# T245Controller_rev1.net
KiCad netlist of a schematic drawn in EAGLE
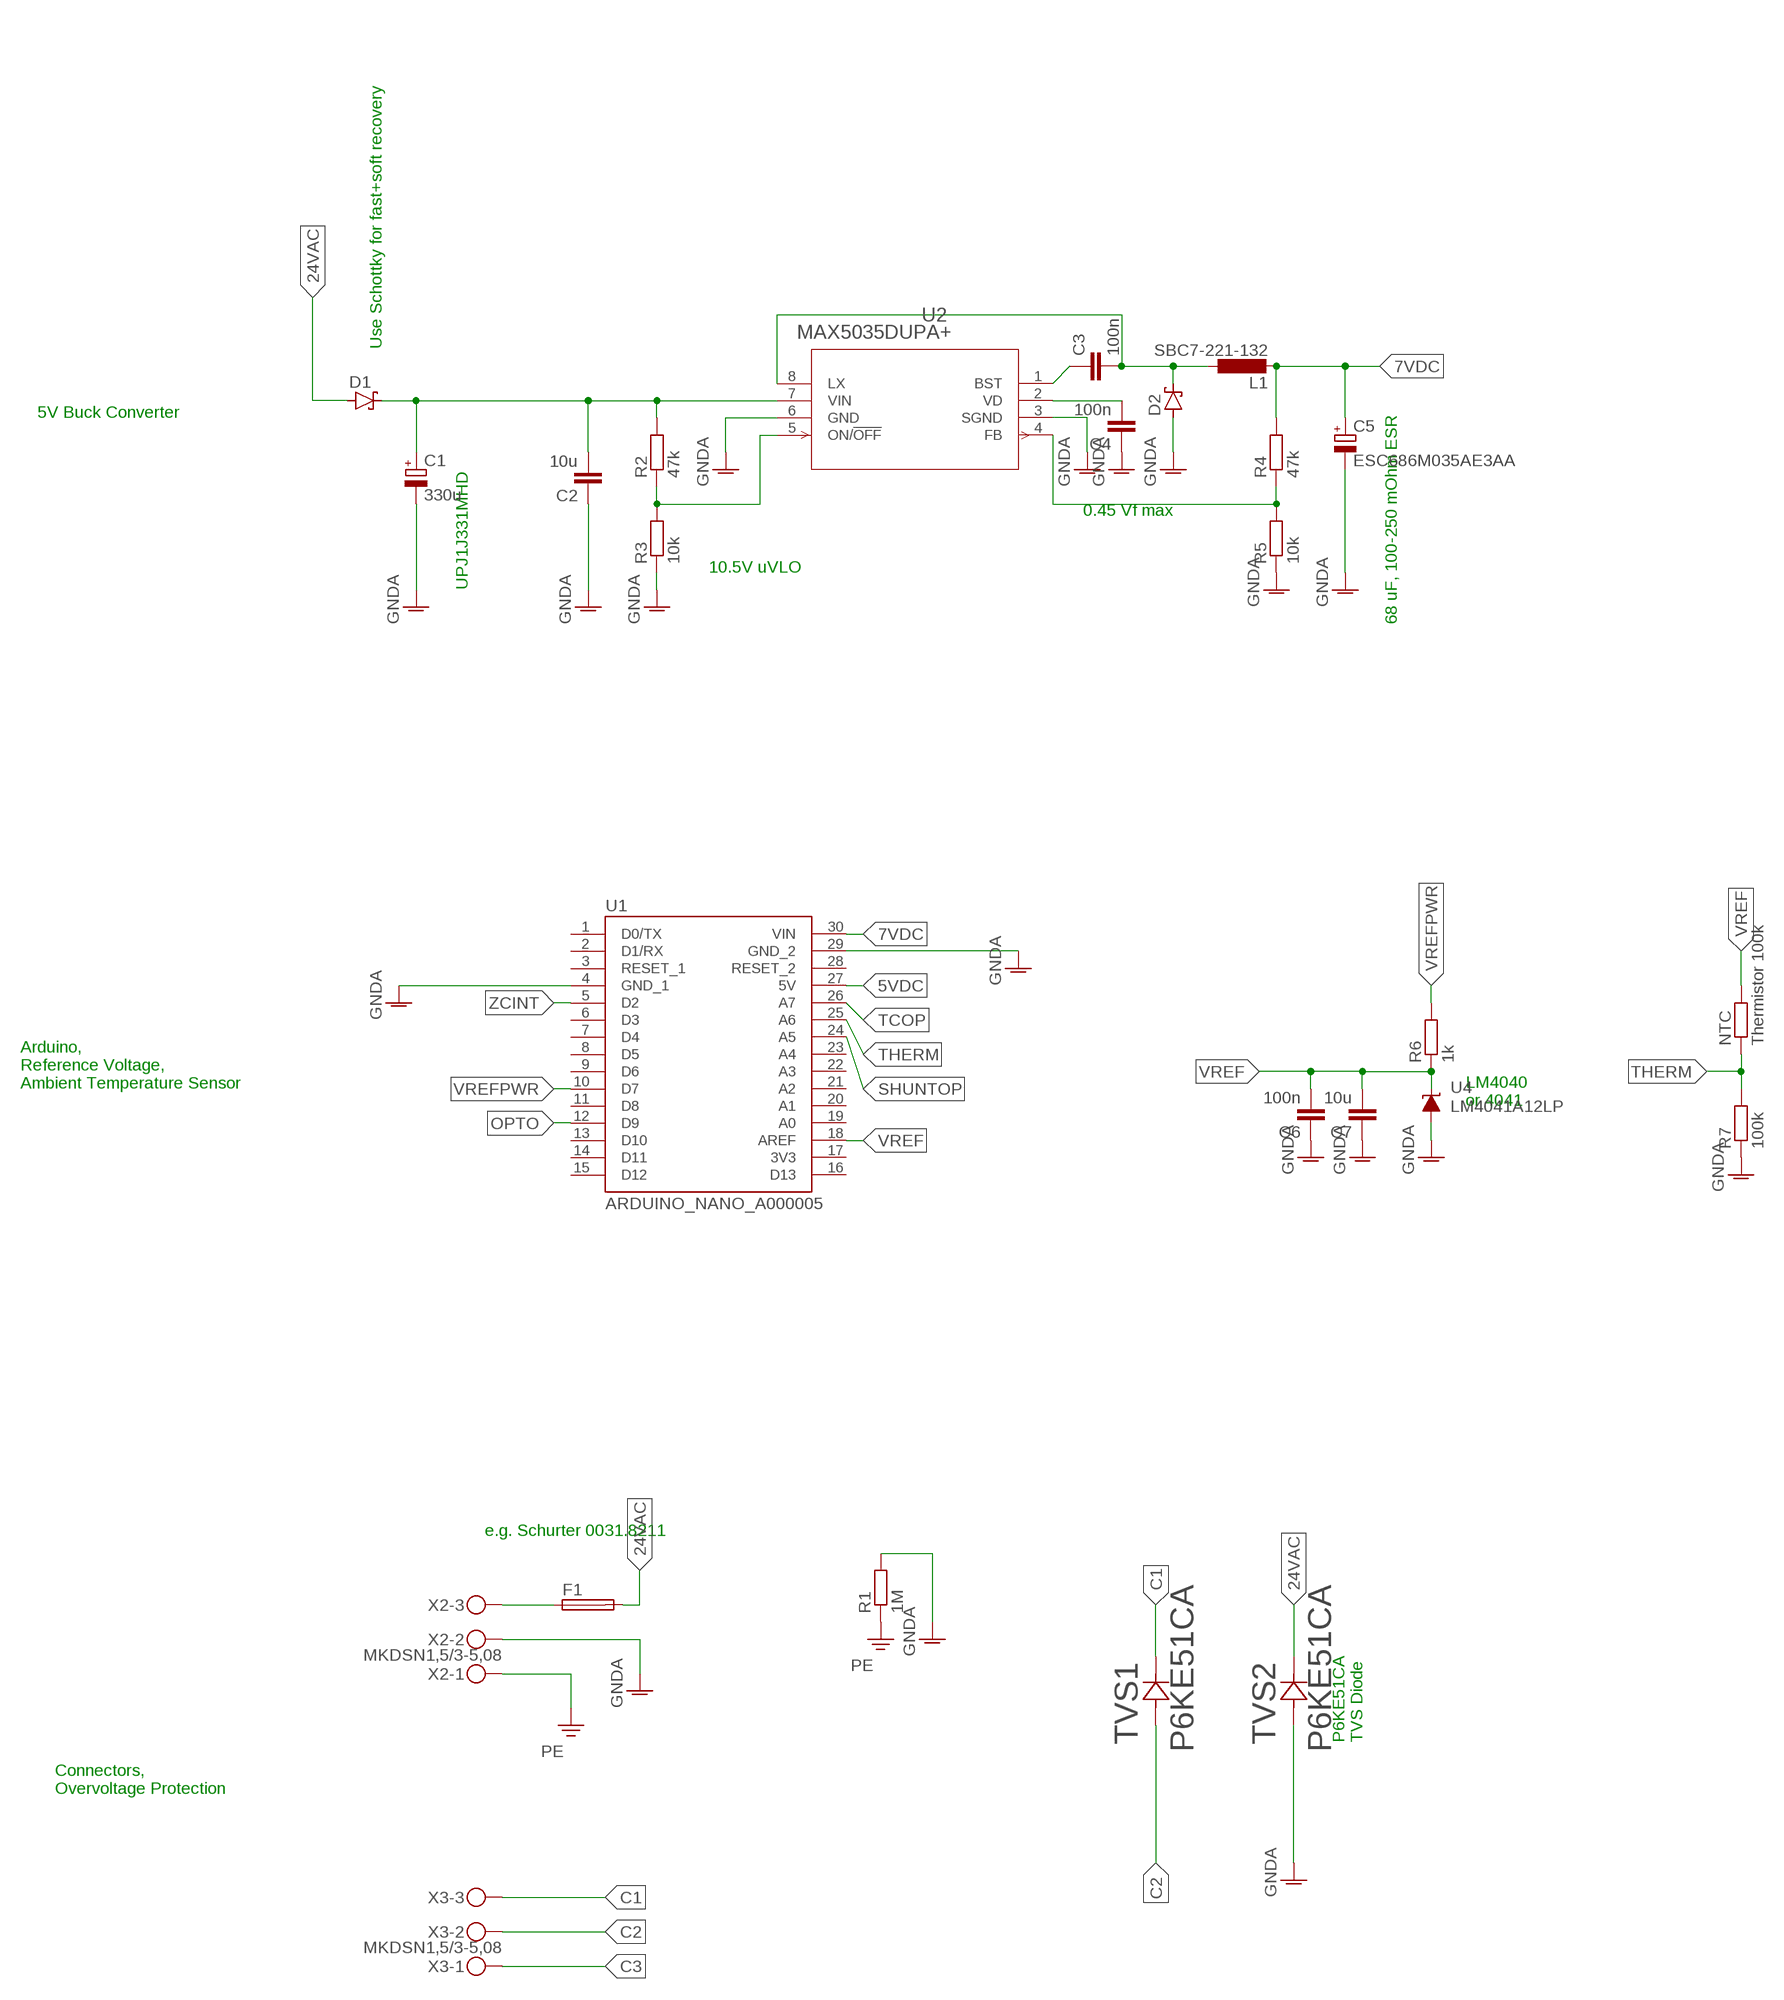
[diagram p0: schematic, sheet 1, part 1 of 2]
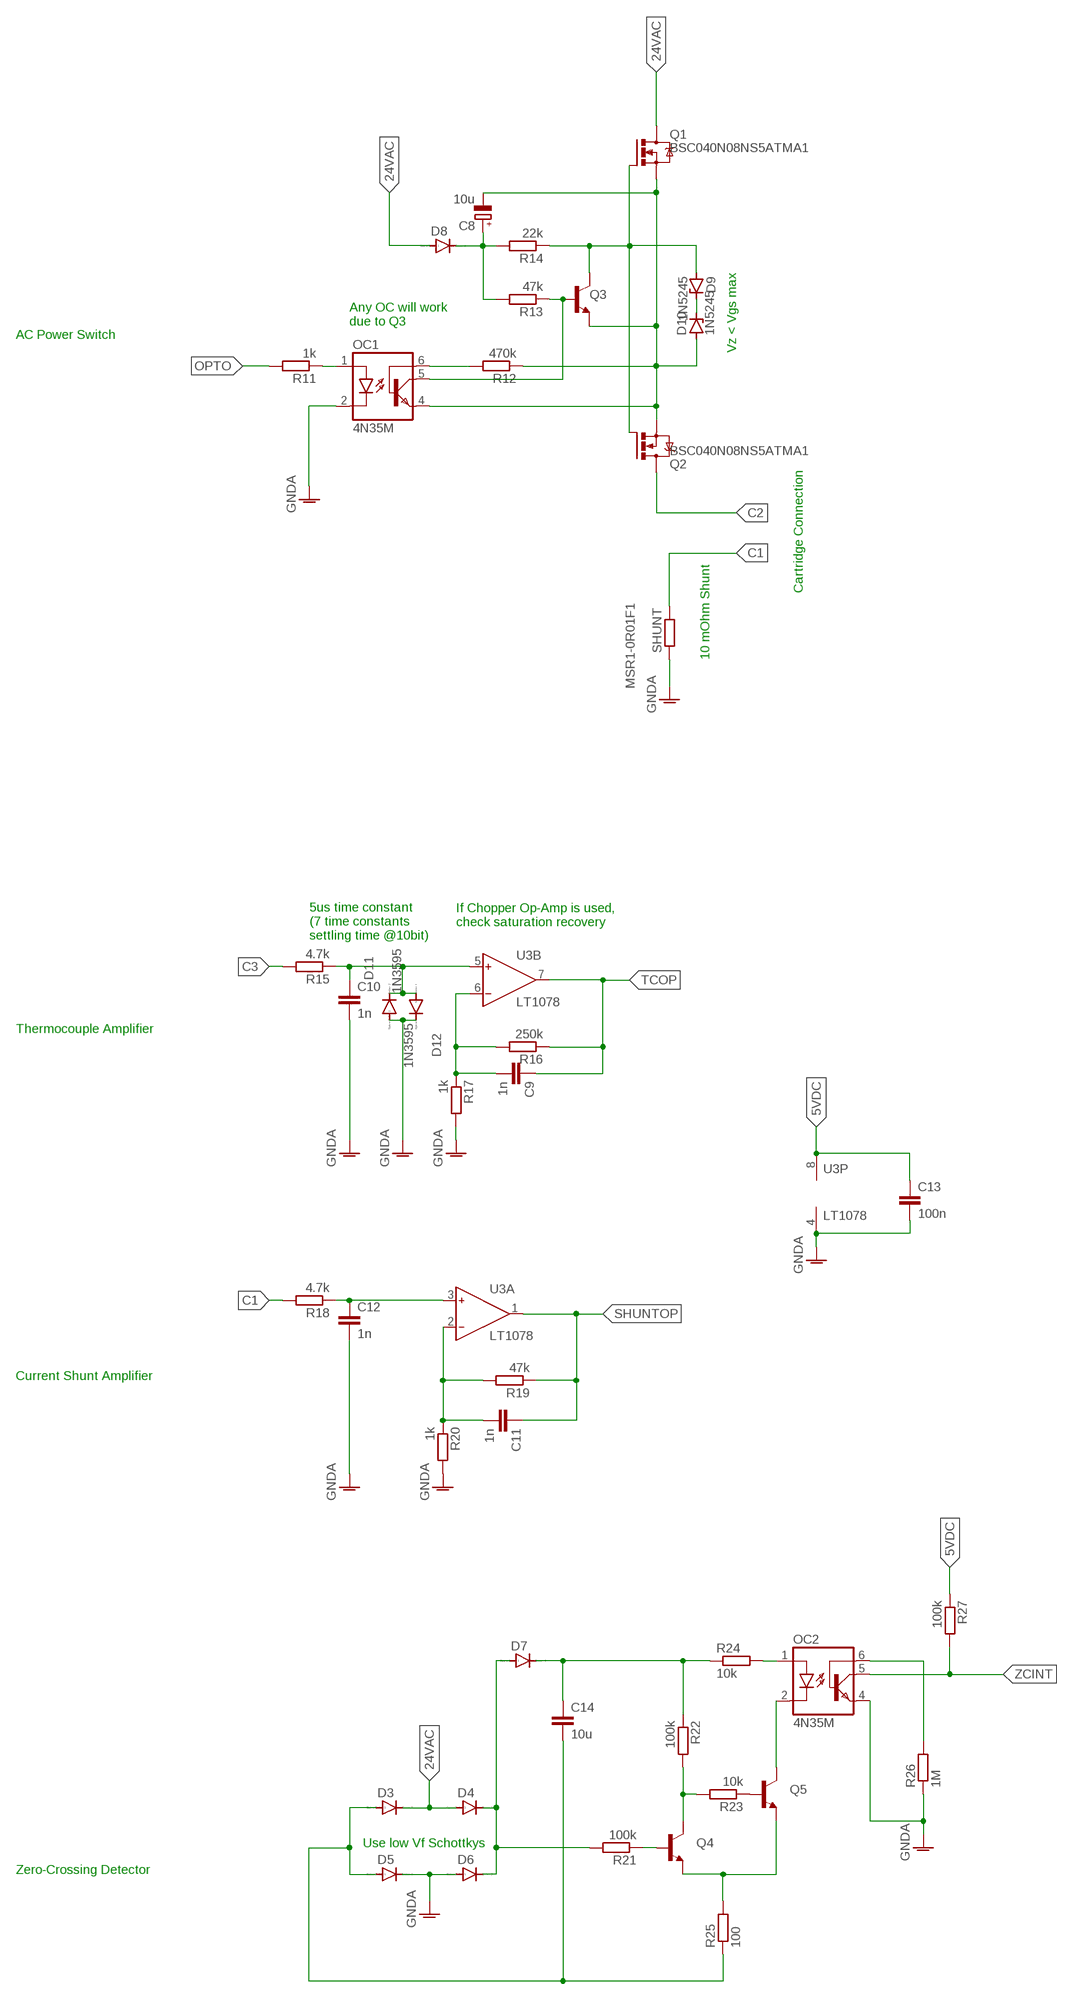
[diagram p1: schematic, sheet 1, part 2 of 2]

(export (version "E")
  (design (tool "Eeschema 10.0.6"))
  (components
    (comp (ref "C1")
      (value "330u")
      (footprint "eagle-import:E5-13")
      (libsource (lib "eagle-import") (part "CPOL-EUE5-13"))
    )
    (comp (ref "C2")
      (value "10u")
      (footprint "eagle-import:C050-024X044")
      (libsource (lib "eagle-import") (part "C-EU050-024X044"))
    )
    (comp (ref "C3")
      (value "100n")
      (footprint "eagle-import:C050-024X044")
      (libsource (lib "eagle-import") (part "C-EU050-024X044"))
    )
    (comp (ref "C4")
      (value "100n")
      (footprint "eagle-import:C050-024X044")
      (libsource (lib "eagle-import") (part "C-EU050-024X044"))
    )
    (comp (ref "C5")
      (value "ESC686M035AE3AA")
      (footprint "eagle-import:E2,5-6")
      (libsource (lib "eagle-import") (part "CPOL-EUE2.5-6"))
    )
    (comp (ref "C6")
      (value "100n")
      (footprint "eagle-import:C050-024X044")
      (libsource (lib "eagle-import") (part "C-EU050-024X044"))
    )
    (comp (ref "C7")
      (value "10u")
      (footprint "eagle-import:C050-024X044")
      (libsource (lib "eagle-import") (part "C-EU050-024X044"))
    )
    (comp (ref "C8")
      (value "10u")
      (footprint "eagle-import:E2,5-6")
      (libsource (lib "eagle-import") (part "CPOL-EUE2.5-6"))
    )
    (comp (ref "C9")
      (value "1n")
      (footprint "eagle-import:C050-024X044")
      (libsource (lib "eagle-import") (part "C-EU050-024X044"))
    )
    (comp (ref "C10")
      (value "1n")
      (footprint "eagle-import:C050-024X044")
      (libsource (lib "eagle-import") (part "C-EU050-024X044"))
    )
    (comp (ref "C11")
      (value "1n")
      (footprint "eagle-import:C050-024X044")
      (libsource (lib "eagle-import") (part "C-EU050-024X044"))
    )
    (comp (ref "C12")
      (value "1n")
      (footprint "eagle-import:C050-024X044")
      (libsource (lib "eagle-import") (part "C-EU050-024X044"))
    )
    (comp (ref "C13")
      (value "100n")
      (footprint "eagle-import:C050-024X044")
      (libsource (lib "eagle-import") (part "C-EU050-024X044"))
    )
    (comp (ref "C14")
      (value "10u")
      (footprint "eagle-import:C050-024X044")
      (libsource (lib "eagle-import") (part "C-EU050-024X044"))
    )
    (comp (ref "D1")
      (value "SCHOTTKY-DIODEF126Z12")
      (footprint "eagle-import:F126Z12")
      (libsource (lib "eagle-import") (part "SCHOTTKY-DIODEF126Z12"))
    )
    (comp (ref "D2")
      (value "SCHOTTKY-DIODEF126Z12")
      (footprint "eagle-import:F126Z12")
      (libsource (lib "eagle-import") (part "SCHOTTKY-DIODEF126Z12"))
    )
    (comp (ref "D3")
      (value "DIODE-D-7.5")
      (footprint "eagle-import:D-7.5")
      (libsource (lib "eagle-import") (part "DIODE-D-7.5"))
    )
    (comp (ref "D4")
      (value "DIODE-D-7.5")
      (footprint "eagle-import:D-7.5")
      (libsource (lib "eagle-import") (part "DIODE-D-7.5"))
    )
    (comp (ref "D5")
      (value "DIODE-D-7.5")
      (footprint "eagle-import:D-7.5")
      (libsource (lib "eagle-import") (part "DIODE-D-7.5"))
    )
    (comp (ref "D6")
      (value "DIODE-D-7.5")
      (footprint "eagle-import:D-7.5")
      (libsource (lib "eagle-import") (part "DIODE-D-7.5"))
    )
    (comp (ref "D7")
      (value "DIODE-D-7.5")
      (footprint "eagle-import:D-7.5")
      (libsource (lib "eagle-import") (part "DIODE-D-7.5"))
    )
    (comp (ref "D8")
      (value "DIODE-D-7.5")
      (footprint "eagle-import:D-7.5")
      (libsource (lib "eagle-import") (part "DIODE-D-7.5"))
    )
    (comp (ref "D9")
      (value "1N5245")
      (footprint "eagle-import:DO41Z10")
      (libsource (lib "eagle-import") (part "ZENER-DIODEDO41Z10"))
    )
    (comp (ref "D10")
      (value "1N5245")
      (footprint "eagle-import:DO41Z10")
      (libsource (lib "eagle-import") (part "ZENER-DIODEDO41Z10"))
    )
    (comp (ref "D11")
      (value "1N3595")
      (footprint "eagle-import:D-7.5")
      (libsource (lib "eagle-import") (part "DIODE-D-7.5"))
    )
    (comp (ref "D12")
      (value "1N3595")
      (footprint "eagle-import:D-7.5")
      (libsource (lib "eagle-import") (part "DIODE-D-7.5"))
    )
    (comp (ref "F1")
      (value "SH22,5A")
      (footprint "eagle-import:SH22,5A")
      (fields (field (name "MPN") "0031.7701.11"))
      (libsource (lib "eagle-import") (part "SH22,5A"))
    )
    (comp (ref "L1")
      (value "SBC7-221-132")
      (footprint "eagle-import:0207_10")
      (libsource (lib "eagle-import") (part "L-EU0207/10"))
    )
    (comp (ref "NTC")
      (value "Thermistor 100k")
      (footprint "eagle-import:0207_10")
      (libsource (lib "eagle-import") (part "rcl_334_R-EU_0207/10"))
    )
    (comp (ref "OC1")
      (value "4N35M")
      (footprint "eagle-import:DIL06")
      (fields (field (name "MPN") "4N35-M"))
      (libsource (lib "eagle-import") (part "4N?M35"))
    )
    (comp (ref "OC2")
      (value "4N35M")
      (footprint "eagle-import:DIL06")
      (fields (field (name "MPN") "4N35-M"))
      (libsource (lib "eagle-import") (part "4N?M35"))
    )
    (comp (ref "Q1")
      (value "BSC040N08NS5ATMA1")
      (footprint "eagle-import:TO220BV")
      (libsource (lib "eagle-import") (part "IRF540"))
    )
    (comp (ref "Q2")
      (value "BSC040N08NS5ATMA1")
      (footprint "eagle-import:TO220BV")
      (libsource (lib "eagle-import") (part "IRF540"))
    )
    (comp (ref "Q3")
      (value "2N5550-NPN-TO92-EBC")
      (footprint "eagle-import:TO92-EBC")
      (libsource (lib "eagle-import") (part "-NPN-TO92-EBC2N5550"))
    )
    (comp (ref "Q4")
      (value "2N5550-NPN-TO92-EBC")
      (footprint "eagle-import:TO92-EBC")
      (libsource (lib "eagle-import") (part "-NPN-TO92-EBC2N5550"))
    )
    (comp (ref "Q5")
      (value "2N5550-NPN-TO92-EBC")
      (footprint "eagle-import:TO92-EBC")
      (libsource (lib "eagle-import") (part "-NPN-TO92-EBC2N5550"))
    )
    (comp (ref "R1")
      (value "1M")
      (footprint "eagle-import:0207_10")
      (libsource (lib "eagle-import") (part "rcl_334_R-EU_0207/10"))
    )
    (comp (ref "R2")
      (value "47k")
      (footprint "eagle-import:0207_10")
      (libsource (lib "eagle-import") (part "rcl_334_R-EU_0207/10"))
    )
    (comp (ref "R3")
      (value "10k")
      (footprint "eagle-import:0207_10")
      (libsource (lib "eagle-import") (part "rcl_334_R-EU_0207/10"))
    )
    (comp (ref "R4")
      (value "47k")
      (footprint "eagle-import:0207_10")
      (libsource (lib "eagle-import") (part "rcl_334_R-EU_0207/10"))
    )
    (comp (ref "R5")
      (value "10k")
      (footprint "eagle-import:0207_10")
      (libsource (lib "eagle-import") (part "rcl_334_R-EU_0207/10"))
    )
    (comp (ref "R6")
      (value "1k")
      (footprint "eagle-import:0207_10")
      (libsource (lib "eagle-import") (part "rcl_334_R-EU_0207/10"))
    )
    (comp (ref "R7")
      (value "100k")
      (footprint "eagle-import:0207_10")
      (libsource (lib "eagle-import") (part "rcl_334_R-EU_0207/10"))
    )
    (comp (ref "R11")
      (value "1k")
      (footprint "eagle-import:0207_10")
      (libsource (lib "eagle-import") (part "rcl_334_R-EU_0207/10"))
    )
    (comp (ref "R12")
      (value "470k")
      (footprint "eagle-import:0207_10")
      (libsource (lib "eagle-import") (part "rcl_334_R-EU_0207/10"))
    )
    (comp (ref "R13")
      (value "47k")
      (footprint "eagle-import:0207_10")
      (libsource (lib "eagle-import") (part "rcl_334_R-EU_0207/10"))
    )
    (comp (ref "R14")
      (value "22k")
      (footprint "eagle-import:0207_10")
      (libsource (lib "eagle-import") (part "rcl_334_R-EU_0207/10"))
    )
    (comp (ref "R15")
      (value "4.7k")
      (footprint "eagle-import:0207_10")
      (libsource (lib "eagle-import") (part "rcl_334_R-EU_0207/10"))
    )
    (comp (ref "R16")
      (value "250k")
      (footprint "eagle-import:0207_10")
      (libsource (lib "eagle-import") (part "rcl_334_R-EU_0207/10"))
    )
    (comp (ref "R17")
      (value "1k")
      (footprint "eagle-import:0207_10")
      (libsource (lib "eagle-import") (part "rcl_334_R-EU_0207/10"))
    )
    (comp (ref "R18")
      (value "4.7k")
      (footprint "eagle-import:0207_10")
      (libsource (lib "eagle-import") (part "rcl_334_R-EU_0207/10"))
    )
    (comp (ref "R19")
      (value "47k")
      (footprint "eagle-import:0207_10")
      (libsource (lib "eagle-import") (part "rcl_334_R-EU_0207/10"))
    )
    (comp (ref "R20")
      (value "1k")
      (footprint "eagle-import:0207_10")
      (libsource (lib "eagle-import") (part "rcl_334_R-EU_0207/10"))
    )
    (comp (ref "R21")
      (value "100k")
      (footprint "eagle-import:0207_10")
      (libsource (lib "eagle-import") (part "rcl_334_R-EU_0207/10"))
    )
    (comp (ref "R22")
      (value "100k")
      (footprint "eagle-import:0207_10")
      (libsource (lib "eagle-import") (part "rcl_334_R-EU_0207/10"))
    )
    (comp (ref "R23")
      (value "10k")
      (footprint "eagle-import:0207_10")
      (libsource (lib "eagle-import") (part "rcl_334_R-EU_0207/10"))
    )
    (comp (ref "R24")
      (value "10k")
      (footprint "eagle-import:0207_10")
      (libsource (lib "eagle-import") (part "rcl_334_R-EU_0207/10"))
    )
    (comp (ref "R25")
      (value "100")
      (footprint "eagle-import:0207_10")
      (libsource (lib "eagle-import") (part "rcl_334_R-EU_0207/10"))
    )
    (comp (ref "R26")
      (value "1M")
      (footprint "eagle-import:0207_10")
      (libsource (lib "eagle-import") (part "rcl_334_R-EU_0207/10"))
    )
    (comp (ref "R27")
      (value "100k")
      (footprint "eagle-import:0207_10")
      (libsource (lib "eagle-import") (part "rcl_334_R-EU_0207/10"))
    )
    (comp (ref "SHUNT")
      (value "MSR1-0R01F1")
      (footprint "eagle-import:0207_12")
      (libsource (lib "eagle-import") (part "R-EU_0207/12"))
    )
    (comp (ref "TVS1")
      (value "P6KE51CA")
      (footprint "eagle-import:P6KESERIES_LTF")
      (libsource (lib "eagle-import") (part "P6KE51CA"))
    )
    (comp (ref "TVS2")
      (value "P6KE51CA")
      (footprint "eagle-import:P6KESERIES_LTF")
      (libsource (lib "eagle-import") (part "P6KE51CA"))
    )
    (comp (ref "U1")
      (value "ARDUINO_NANO_A000005")
      (footprint "eagle-import:MODULE_A000005")
      (fields (field (name "MF") "Arduino") (field (name "MP") "A000005"))
      (libsource (lib "eagle-import") (part "ARDUINO_NANO_A000005"))
    )
    (comp (ref "U2")
      (value "MAX5035DUPA+")
      (footprint "eagle-import:21-0043_P8+3_MXM")
      (fields (field (name "MANUFACTURER_PART_NUMBER") "max5035dupa+"))
      (libsource (lib "eagle-import") (part "MAX5035DUPA+"))
    )
    (comp (ref "U3")
      (value "LT1078")
      (footprint "eagle-import:DIL08")
      (libsource (lib "eagle-import") (part "AD8066N"))
    )
    (comp (ref "U4")
      (value "LM4041A12LP")
      (footprint "eagle-import:LP_O-PBCY-W3")
      (libsource (lib "eagle-import") (part "LM4041LPA12"))
    )
    (comp (ref "X2")
      (value "MKDSN1,5/3-5,08")
      (footprint "eagle-import:MKDSN1,5_3-5,08")
      (libsource (lib "eagle-import") (part "MKDSN1,5/3-5,08"))
    )
    (comp (ref "X3")
      (value "MKDSN1,5/3-5,08")
      (footprint "eagle-import:MKDSN1,5_3-5,08")
      (libsource (lib "eagle-import") (part "MKDSN1,5/3-5,08"))
    )
  )
  (nets
    (net (code "1") (name "3V3") (class "Default")
      (node (ref "U1") (pin "17") (pinfunction "3V3_17") (pintype "power_in"))
    )
    (net (code "2") (name "5VDC") (class "Default")
      (node (ref "C13") (pin "1") (pinfunction "1_1") (pintype "passive"))
      (node (ref "R27") (pin "1") (pinfunction "1_1") (pintype "passive"))
      (node (ref "U1") (pin "27") (pinfunction "5V_27") (pintype "power_in"))
      (node (ref "U3") (pin "8") (pinfunction "V+_8") (pintype "power_in"))
    )
    (net (code "3") (name "7VDC") (class "Default")
      (node (ref "C5") (pin "+") (pinfunction "+_+") (pintype "passive"))
      (node (ref "L1") (pin "2") (pinfunction "2_2") (pintype "passive"))
      (node (ref "R4") (pin "2") (pinfunction "2_2") (pintype "passive"))
      (node (ref "U1") (pin "30") (pinfunction "VIN_30") (pintype "power_in"))
    )
    (net (code "4") (name "24VAC") (class "Default")
      (node (ref "D1") (pin "A") (pinfunction "A_A") (pintype "passive"))
      (node (ref "D3") (pin "C") (pinfunction "C_C") (pintype "passive"))
      (node (ref "D4") (pin "A") (pinfunction "A_A") (pintype "passive"))
      (node (ref "D8") (pin "A") (pinfunction "A_A") (pintype "passive"))
      (node (ref "F1") (pin "2") (pinfunction "2_2") (pintype "passive"))
      (node (ref "Q1") (pin "D") (pinfunction "D_D") (pintype "passive"))
      (node (ref "TVS2") (pin "1") (pinfunction "11_1") (pintype "passive"))
    )
    (net (code "5") (name "C1") (class "Default")
      (node (ref "R18") (pin "2") (pinfunction "2_2") (pintype "passive"))
      (node (ref "SHUNT") (pin "2") (pinfunction "2_2") (pintype "passive"))
      (node (ref "TVS1") (pin "1") (pinfunction "11_1") (pintype "passive"))
      (node (ref "X3") (pin "3") (pinfunction "KL_3") (pintype "passive"))
    )
    (net (code "6") (name "C2") (class "Default")
      (node (ref "Q2") (pin "D") (pinfunction "D_D") (pintype "passive"))
      (node (ref "TVS1") (pin "2") (pinfunction "12_2") (pintype "passive"))
      (node (ref "X3") (pin "2") (pinfunction "KL_2") (pintype "passive"))
    )
    (net (code "7") (name "C3") (class "Default")
      (node (ref "R15") (pin "2") (pinfunction "2_2") (pintype "passive"))
      (node (ref "X3") (pin "1") (pinfunction "KL_1") (pintype "passive"))
    )
    (net (code "8") (name "GNDA") (class "Default")
      (node (ref "C1") (pin "-") (pinfunction "-_-") (pintype "passive"))
      (node (ref "C10") (pin "2") (pinfunction "2_2") (pintype "passive"))
      (node (ref "C12") (pin "2") (pinfunction "2_2") (pintype "passive"))
      (node (ref "C13") (pin "2") (pinfunction "2_2") (pintype "passive"))
      (node (ref "C2") (pin "1") (pinfunction "1_1") (pintype "passive"))
      (node (ref "C4") (pin "1") (pinfunction "1_1") (pintype "passive"))
      (node (ref "C5") (pin "-") (pinfunction "-_-") (pintype "passive"))
      (node (ref "C6") (pin "1") (pinfunction "1_1") (pintype "passive"))
      (node (ref "C7") (pin "1") (pinfunction "1_1") (pintype "passive"))
      (node (ref "D11") (pin "A") (pinfunction "A_A") (pintype "passive"))
      (node (ref "D12") (pin "C") (pinfunction "C_C") (pintype "passive"))
      (node (ref "D2") (pin "A") (pinfunction "A_A") (pintype "passive"))
      (node (ref "D5") (pin "C") (pinfunction "C_C") (pintype "passive"))
      (node (ref "D6") (pin "A") (pinfunction "A_A") (pintype "passive"))
      (node (ref "OC1") (pin "2") (pinfunction "C_2") (pintype "passive"))
      (node (ref "OC2") (pin "4") (pinfunction "EMI_4") (pintype "passive"))
      (node (ref "R1") (pin "2") (pinfunction "2_2") (pintype "passive"))
      (node (ref "R17") (pin "2") (pinfunction "2_2") (pintype "passive"))
      (node (ref "R20") (pin "2") (pinfunction "2_2") (pintype "passive"))
      (node (ref "R26") (pin "1") (pinfunction "1_1") (pintype "passive"))
      (node (ref "R3") (pin "1") (pinfunction "1_1") (pintype "passive"))
      (node (ref "R5") (pin "1") (pinfunction "1_1") (pintype "passive"))
      (node (ref "R7") (pin "1") (pinfunction "1_1") (pintype "passive"))
      (node (ref "SHUNT") (pin "1") (pinfunction "1_1") (pintype "passive"))
      (node (ref "TVS2") (pin "2") (pinfunction "12_2") (pintype "passive"))
      (node (ref "U1") (pin "29") (pinfunction "GND_2_29") (pintype "power_in"))
      (node (ref "U1") (pin "4") (pinfunction "GND_1_4") (pintype "power_in"))
      (node (ref "U2") (pin "3") (pinfunction "SGND_3") (pintype "power_in"))
      (node (ref "U2") (pin "6") (pinfunction "GND_6") (pintype "power_in"))
      (node (ref "U3") (pin "4") (pinfunction "V-_4") (pintype "power_in"))
      (node (ref "U4") (pin "3") (pinfunction "A_3") (pintype "passive"))
      (node (ref "X2") (pin "2") (pinfunction "KL_2") (pintype "passive"))
    )
    (net (code "9") (name "Net-(C8-Pad+)") (class "Default")
      (node (ref "C8") (pin "+") (pinfunction "+_+") (pintype "passive"))
      (node (ref "D8") (pin "C") (pinfunction "C_C") (pintype "passive"))
      (node (ref "R13") (pin "2") (pinfunction "2_2") (pintype "passive"))
      (node (ref "R14") (pin "2") (pinfunction "2_2") (pintype "passive"))
    )
    (net (code "10") (name "Net-(C14-Pad1)") (class "Default")
      (node (ref "C14") (pin "1") (pinfunction "1_1") (pintype "passive"))
      (node (ref "D7") (pin "C") (pinfunction "C_C") (pintype "passive"))
      (node (ref "R22") (pin "1") (pinfunction "1_1") (pintype "passive"))
      (node (ref "R24") (pin "1") (pinfunction "1_1") (pintype "passive"))
    )
    (net (code "11") (name "Net-(C14-Pad2)") (class "Default")
      (node (ref "C14") (pin "2") (pinfunction "2_2") (pintype "passive"))
      (node (ref "D3") (pin "A") (pinfunction "A_A") (pintype "passive"))
      (node (ref "D5") (pin "A") (pinfunction "A_A") (pintype "passive"))
      (node (ref "R25") (pin "1") (pinfunction "1_1") (pintype "passive"))
    )
    (net (code "12") (name "Net-(D4-PadC)") (class "Default")
      (node (ref "D4") (pin "C") (pinfunction "C_C") (pintype "passive"))
      (node (ref "D6") (pin "C") (pinfunction "C_C") (pintype "passive"))
      (node (ref "D7") (pin "A") (pinfunction "A_A") (pintype "passive"))
      (node (ref "R21") (pin "2") (pinfunction "2_2") (pintype "passive"))
    )
    (net (code "13") (name "Net-(D9-PadA)") (class "Default")
      (node (ref "D9") (pin "A") (pinfunction "A_A") (pintype "passive"))
      (node (ref "Q1") (pin "G") (pinfunction "G_G") (pintype "passive"))
      (node (ref "Q2") (pin "G") (pinfunction "G_G") (pintype "passive"))
      (node (ref "Q3") (pin "C") (pinfunction "C_C") (pintype "passive"))
      (node (ref "R14") (pin "1") (pinfunction "1_1") (pintype "passive"))
    )
    (net (code "14") (name "Net-(D10-PadC)") (class "Default")
      (node (ref "D10") (pin "C") (pinfunction "C_C") (pintype "passive"))
      (node (ref "D9") (pin "C") (pinfunction "C_C") (pintype "passive"))
    )
    (net (code "15") (name "Net-(OC1-A)") (class "Default")
      (node (ref "OC1") (pin "1") (pinfunction "A_1") (pintype "passive"))
      (node (ref "R11") (pin "1") (pinfunction "1_1") (pintype "passive"))
    )
    (net (code "16") (name "Net-(OC1-BAS)") (class "Default")
      (node (ref "OC1") (pin "6") (pinfunction "BAS_6") (pintype "passive"))
      (node (ref "R12") (pin "2") (pinfunction "2_2") (pintype "passive"))
    )
    (net (code "17") (name "Net-(OC1-COL)") (class "Default")
      (node (ref "OC1") (pin "5") (pinfunction "COL_5") (pintype "passive"))
      (node (ref "Q3") (pin "B") (pinfunction "B_B") (pintype "passive"))
      (node (ref "R13") (pin "1") (pinfunction "1_1") (pintype "passive"))
    )
    (net (code "18") (name "Net-(OC1-EMI)") (class "Default")
      (node (ref "C8") (pin "-") (pinfunction "-_-") (pintype "passive"))
      (node (ref "D10") (pin "A") (pinfunction "A_A") (pintype "passive"))
      (node (ref "OC1") (pin "4") (pinfunction "EMI_4") (pintype "passive"))
      (node (ref "Q1") (pin "S") (pinfunction "S_S") (pintype "passive"))
      (node (ref "Q2") (pin "S") (pinfunction "S_S") (pintype "passive"))
      (node (ref "Q3") (pin "E") (pinfunction "E_E") (pintype "passive"))
      (node (ref "R12") (pin "1") (pinfunction "1_1") (pintype "passive"))
    )
    (net (code "19") (name "Net-(OC2-A)") (class "Default")
      (node (ref "OC2") (pin "1") (pinfunction "A_1") (pintype "passive"))
      (node (ref "R24") (pin "2") (pinfunction "2_2") (pintype "passive"))
    )
    (net (code "20") (name "Net-(OC2-BAS)") (class "Default")
      (node (ref "OC2") (pin "6") (pinfunction "BAS_6") (pintype "passive"))
      (node (ref "R26") (pin "2") (pinfunction "2_2") (pintype "passive"))
    )
    (net (code "21") (name "Net-(OC2-C)") (class "Default")
      (node (ref "OC2") (pin "2") (pinfunction "C_2") (pintype "passive"))
      (node (ref "Q5") (pin "C") (pinfunction "C_C") (pintype "passive"))
    )
    (net (code "22") (name "Net-(Q4-PadB)") (class "Default")
      (node (ref "Q4") (pin "B") (pinfunction "B_B") (pintype "passive"))
      (node (ref "R21") (pin "1") (pinfunction "1_1") (pintype "passive"))
    )
    (net (code "23") (name "Net-(Q4-PadC)") (class "Default")
      (node (ref "Q4") (pin "C") (pinfunction "C_C") (pintype "passive"))
      (node (ref "R22") (pin "2") (pinfunction "2_2") (pintype "passive"))
      (node (ref "R23") (pin "2") (pinfunction "2_2") (pintype "passive"))
    )
    (net (code "24") (name "Net-(Q4-PadE)") (class "Default")
      (node (ref "Q4") (pin "E") (pinfunction "E_E") (pintype "passive"))
      (node (ref "Q5") (pin "E") (pinfunction "E_E") (pintype "passive"))
      (node (ref "R25") (pin "2") (pinfunction "2_2") (pintype "passive"))
    )
    (net (code "25") (name "Net-(Q5-PadB)") (class "Default")
      (node (ref "Q5") (pin "B") (pinfunction "B_B") (pintype "passive"))
      (node (ref "R23") (pin "1") (pinfunction "1_1") (pintype "passive"))
    )
    (net (code "26") (name "Net-(U2-BST)") (class "Default")
      (node (ref "C3") (pin "1") (pinfunction "1_1") (pintype "passive"))
      (node (ref "U2") (pin "1") (pinfunction "BST_1") (pintype "passive"))
    )
    (net (code "27") (name "Net-(U2-FB)") (class "Default")
      (node (ref "R4") (pin "1") (pinfunction "1_1") (pintype "passive"))
      (node (ref "R5") (pin "2") (pinfunction "2_2") (pintype "passive"))
      (node (ref "U2") (pin "4") (pinfunction "FB_4") (pintype "output"))
    )
    (net (code "28") (name "Net-(U2-LX)") (class "Default")
      (node (ref "C3") (pin "2") (pinfunction "2_2") (pintype "passive"))
      (node (ref "D2") (pin "C") (pinfunction "C_C") (pintype "passive"))
      (node (ref "L1") (pin "1") (pinfunction "1_1") (pintype "passive"))
      (node (ref "U2") (pin "8") (pinfunction "LX_8") (pintype "passive"))
    )
    (net (code "29") (name "Net-(U2-ON{slash}~{OFF})") (class "Default")
      (node (ref "R2") (pin "1") (pinfunction "1_1") (pintype "passive"))
      (node (ref "R3") (pin "2") (pinfunction "2_2") (pintype "passive"))
      (node (ref "U2") (pin "5") (pinfunction "ON/~{OFF}_5") (pintype "input"))
    )
    (net (code "30") (name "Net-(U2-VD)") (class "Default")
      (node (ref "C4") (pin "2") (pinfunction "2_2") (pintype "passive"))
      (node (ref "U2") (pin "2") (pinfunction "VD_2") (pintype "power_in"))
    )
    (net (code "31") (name "Net-(U2-VIN)") (class "Default")
      (node (ref "C1") (pin "+") (pinfunction "+_+") (pintype "passive"))
      (node (ref "C2") (pin "2") (pinfunction "2_2") (pintype "passive"))
      (node (ref "D1") (pin "C") (pinfunction "C_C") (pintype "passive"))
      (node (ref "R2") (pin "2") (pinfunction "2_2") (pintype "passive"))
      (node (ref "U2") (pin "7") (pinfunction "VIN_7") (pintype "power_in"))
    )
    (net (code "32") (name "Net-(U3A-IN+)") (class "Default")
      (node (ref "C12") (pin "1") (pinfunction "1_1") (pintype "passive"))
      (node (ref "R18") (pin "1") (pinfunction "1_1") (pintype "passive"))
      (node (ref "U3") (pin "3") (pinfunction "IN+_3") (pintype "input"))
    )
    (net (code "33") (name "Net-(U3A-IN-)") (class "Default")
      (node (ref "C11") (pin "2") (pinfunction "2_2") (pintype "passive"))
      (node (ref "R19") (pin "2") (pinfunction "2_2") (pintype "passive"))
      (node (ref "R20") (pin "1") (pinfunction "1_1") (pintype "passive"))
      (node (ref "U3") (pin "2") (pinfunction "IN-_2") (pintype "input"))
    )
    (net (code "34") (name "Net-(U3B-IN+)") (class "Default")
      (node (ref "C10") (pin "1") (pinfunction "1_1") (pintype "passive"))
      (node (ref "D11") (pin "C") (pinfunction "C_C") (pintype "passive"))
      (node (ref "D12") (pin "A") (pinfunction "A_A") (pintype "passive"))
      (node (ref "R15") (pin "1") (pinfunction "1_1") (pintype "passive"))
      (node (ref "U3") (pin "5") (pinfunction "IN+_5") (pintype "input"))
    )
    (net (code "35") (name "Net-(U3B-IN-)") (class "Default")
      (node (ref "C9") (pin "2") (pinfunction "2_2") (pintype "passive"))
      (node (ref "R16") (pin "2") (pinfunction "2_2") (pintype "passive"))
      (node (ref "R17") (pin "1") (pinfunction "1_1") (pintype "passive"))
      (node (ref "U3") (pin "6") (pinfunction "IN-_6") (pintype "input"))
    )
    (net (code "36") (name "Net-(X2C-KL)") (class "Default")
      (node (ref "F1") (pin "1") (pinfunction "1_1") (pintype "passive"))
      (node (ref "X2") (pin "3") (pinfunction "KL_3") (pintype "passive"))
    )
    (net (code "37") (name "OPTO") (class "Default")
      (node (ref "R11") (pin "2") (pinfunction "2_2") (pintype "passive"))
      (node (ref "U1") (pin "12") (pinfunction "D9_12") (pintype "bidirectional"))
    )
    (net (code "38") (name "PE") (class "Default")
      (node (ref "R1") (pin "1") (pinfunction "1_1") (pintype "passive"))
      (node (ref "X2") (pin "1") (pinfunction "KL_1") (pintype "passive"))
    )
    (net (code "39") (name "SHUNTOP") (class "Default")
      (node (ref "C11") (pin "1") (pinfunction "1_1") (pintype "passive"))
      (node (ref "R19") (pin "1") (pinfunction "1_1") (pintype "passive"))
      (node (ref "U1") (pin "24") (pinfunction "A5_24") (pintype "input"))
      (node (ref "U3") (pin "1") (pinfunction "OUT_1") (pintype "output"))
    )
    (net (code "40") (name "TCOP") (class "Default")
      (node (ref "C9") (pin "1") (pinfunction "1_1") (pintype "passive"))
      (node (ref "R16") (pin "1") (pinfunction "1_1") (pintype "passive"))
      (node (ref "U1") (pin "26") (pinfunction "A7_26") (pintype "input"))
      (node (ref "U3") (pin "7") (pinfunction "OUT_7") (pintype "output"))
    )
    (net (code "41") (name "THERM") (class "Default")
      (node (ref "NTC") (pin "1") (pinfunction "1_1") (pintype "passive"))
      (node (ref "R7") (pin "2") (pinfunction "2_2") (pintype "passive"))
      (node (ref "U1") (pin "25") (pinfunction "A6_25") (pintype "input"))
    )
    (net (code "42") (name "VREF") (class "Default")
      (node (ref "C6") (pin "2") (pinfunction "2_2") (pintype "passive"))
      (node (ref "C7") (pin "2") (pinfunction "2_2") (pintype "passive"))
      (node (ref "NTC") (pin "2") (pinfunction "2_2") (pintype "passive"))
      (node (ref "R6") (pin "1") (pinfunction "1_1") (pintype "passive"))
      (node (ref "U1") (pin "18") (pinfunction "AREF_18") (pintype "input"))
      (node (ref "U4") (pin "2") (pinfunction "C_2") (pintype "passive"))
    )
    (net (code "43") (name "VREFPWR") (class "Default")
      (node (ref "R6") (pin "2") (pinfunction "2_2") (pintype "passive"))
      (node (ref "U1") (pin "10") (pinfunction "D7_10") (pintype "bidirectional"))
    )
    (net (code "44") (name "ZCINT") (class "Default")
      (node (ref "OC2") (pin "5") (pinfunction "COL_5") (pintype "passive"))
      (node (ref "R27") (pin "2") (pinfunction "2_2") (pintype "passive"))
      (node (ref "U1") (pin "5") (pinfunction "D2_5") (pintype "bidirectional"))
    )
    (net (code "45") (name "unconnected-(U1-A0-Pad19)") (class "Default")
      (node (ref "U1") (pin "19") (pinfunction "A0_19") (pintype "input"))
    )
    (net (code "46") (name "unconnected-(U1-A1-Pad20)") (class "Default")
      (node (ref "U1") (pin "20") (pinfunction "A1_20") (pintype "input"))
    )
    (net (code "47") (name "unconnected-(U1-A2-Pad21)") (class "Default")
      (node (ref "U1") (pin "21") (pinfunction "A2_21") (pintype "input"))
    )
    (net (code "48") (name "unconnected-(U1-A3-Pad22)") (class "Default")
      (node (ref "U1") (pin "22") (pinfunction "A3_22") (pintype "input"))
    )
    (net (code "49") (name "unconnected-(U1-A4-Pad23)") (class "Default")
      (node (ref "U1") (pin "23") (pinfunction "A4_23") (pintype "input"))
    )
    (net (code "50") (name "unconnected-(U1-D0{slash}TX-Pad1)") (class "Default")
      (node (ref "U1") (pin "1") (pinfunction "D0/TX_1") (pintype "bidirectional"))
    )
    (net (code "51") (name "unconnected-(U1-D1{slash}RX-Pad2)") (class "Default")
      (node (ref "U1") (pin "2") (pinfunction "D1/RX_2") (pintype "bidirectional"))
    )
    (net (code "52") (name "unconnected-(U1-D3-Pad6)") (class "Default")
      (node (ref "U1") (pin "6") (pinfunction "D3_6") (pintype "bidirectional"))
    )
    (net (code "53") (name "unconnected-(U1-D4-Pad7)") (class "Default")
      (node (ref "U1") (pin "7") (pinfunction "D4_7") (pintype "bidirectional"))
    )
    (net (code "54") (name "unconnected-(U1-D5-Pad8)") (class "Default")
      (node (ref "U1") (pin "8") (pinfunction "D5_8") (pintype "bidirectional"))
    )
    (net (code "55") (name "unconnected-(U1-D6-Pad9)") (class "Default")
      (node (ref "U1") (pin "9") (pinfunction "D6_9") (pintype "bidirectional"))
    )
    (net (code "56") (name "unconnected-(U1-D8-Pad11)") (class "Default")
      (node (ref "U1") (pin "11") (pinfunction "D8_11") (pintype "bidirectional"))
    )
    (net (code "57") (name "unconnected-(U1-D10-Pad13)") (class "Default")
      (node (ref "U1") (pin "13") (pinfunction "D10_13") (pintype "bidirectional"))
    )
    (net (code "58") (name "unconnected-(U1-D11-Pad14)") (class "Default")
      (node (ref "U1") (pin "14") (pinfunction "D11_14") (pintype "bidirectional"))
    )
    (net (code "59") (name "unconnected-(U1-D12-Pad15)") (class "Default")
      (node (ref "U1") (pin "15") (pinfunction "D12_15") (pintype "bidirectional"))
    )
    (net (code "60") (name "unconnected-(U1-D13-Pad16)") (class "Default")
      (node (ref "U1") (pin "16") (pinfunction "D13_16") (pintype "bidirectional"))
    )
    (net (code "61") (name "unconnected-(U1-RESET_1-Pad3)") (class "Default")
      (node (ref "U1") (pin "3") (pinfunction "RESET_1_3") (pintype "input"))
    )
    (net (code "62") (name "unconnected-(U1-RESET_2-Pad28)") (class "Default")
      (node (ref "U1") (pin "28") (pinfunction "RESET_2_28") (pintype "input"))
    )
  )
)
